# Module_blk.net
KiCad netlist of a schematic drawn in Altium Designer
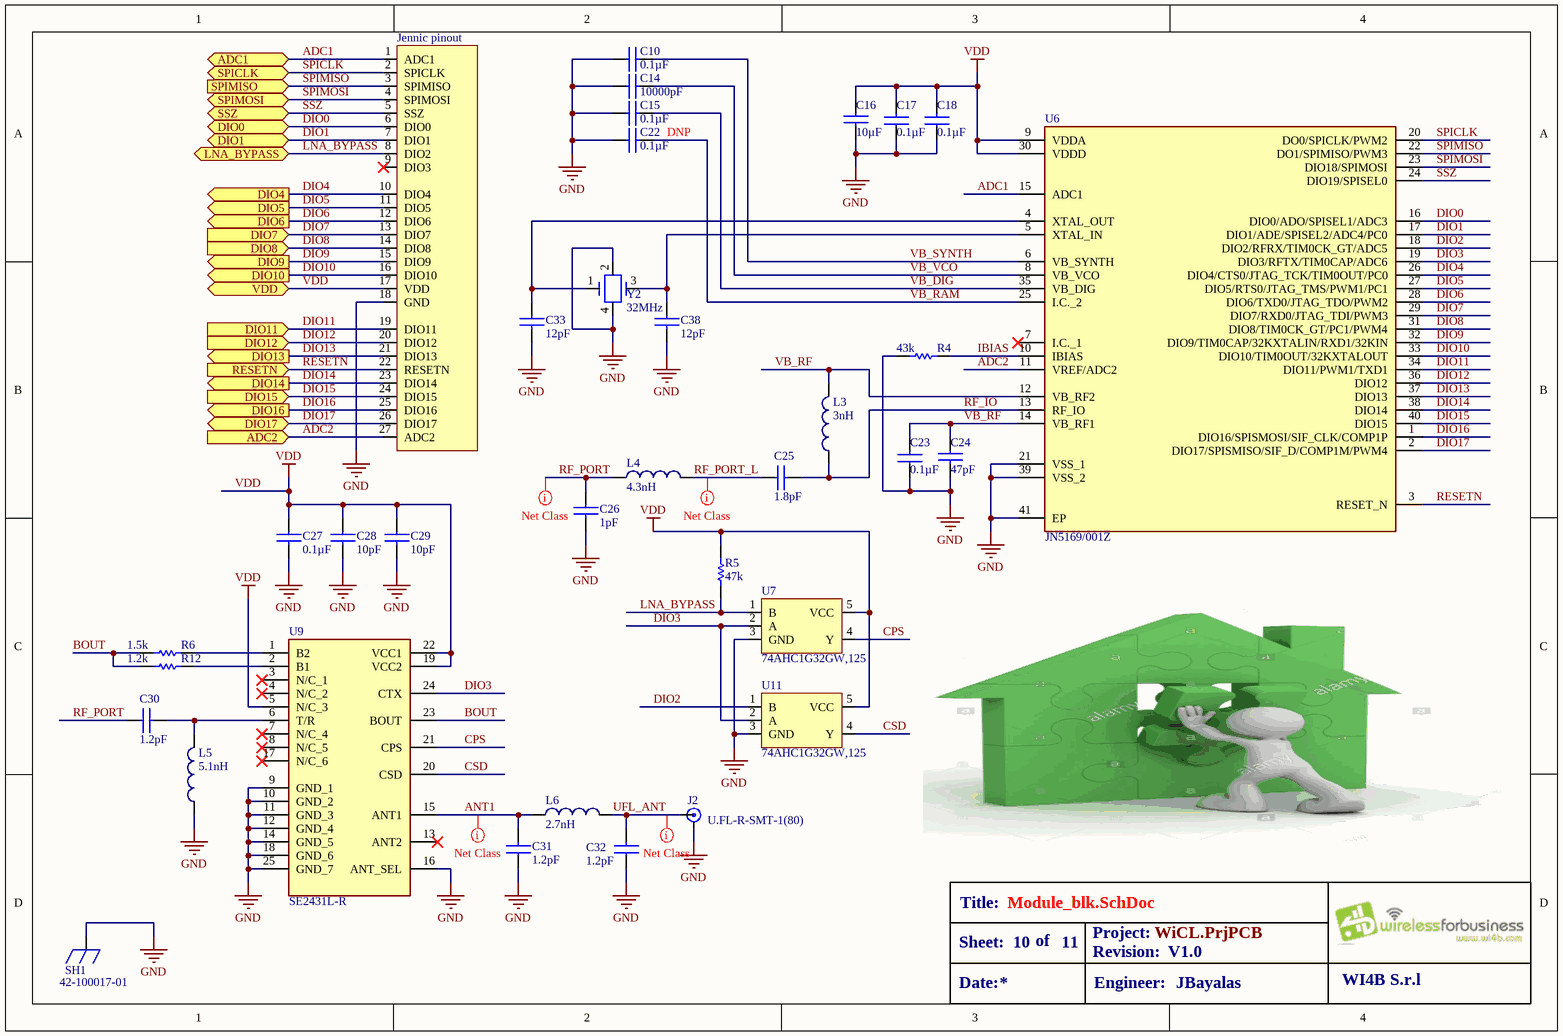
[diagram p0: Module_blk.SchDoc]

(export (version "E")
  (design (tool "Eeschema 10.0.6"))
  (components
    (comp (ref "C10")
      (value "0.1µF")
      (footprint "C0402")
      (description "CAP CER 0.1UF 10V 10% X5R 0402")
      (fields (field (name "MPN") "GRM155R61A104KA01D"))
      (libsource (lib "Capacitor") (part "GRM155R61A104KA01D"))
    )
    (comp (ref "C14")
      (value "10000pF")
      (footprint "C0402")
      (description "CAP CER 10000PF 25V X7R 0402")
      (fields (field (name "MPN") "GRM155R71E103KA01D"))
      (libsource (lib "Capacitor") (part "GRM155R71E103KA01D"))
    )
    (comp (ref "C15")
      (value "0.1µF")
      (footprint "C0402")
      (description "CAP CER 0.1UF 10V 10% X5R 0402")
      (fields (field (name "MPN") "GRM155R61A104KA01D"))
      (libsource (lib "Capacitor") (part "GRM155R61A104KA01D"))
    )
    (comp (ref "C16")
      (value "10µF")
      (footprint "CAPC2012X135N")
      (description "CAP CER 10UF 10V X5R 0805")
      (fields (field (name "MPN") "GRT21BR61A106KE01L"))
      (libsource (lib "Capacitor") (part "GRT21BR61A106KE01L"))
    )
    (comp (ref "C17")
      (value "0.1µF")
      (footprint "C0402")
      (description "CAP CER 0.1UF 10V 10% X5R 0402")
      (fields (field (name "MPN") "GRM155R61A104KA01D"))
      (libsource (lib "Capacitor") (part "GRM155R61A104KA01D"))
    )
    (comp (ref "C18")
      (value "0.1µF")
      (footprint "C0402")
      (description "CAP CER 0.1UF 10V 10% X5R 0402")
      (fields (field (name "MPN") "GRM155R61A104KA01D"))
      (libsource (lib "Capacitor") (part "GRM155R61A104KA01D"))
    )
    (comp (ref "C22")
      (value "0.1µF")
      (footprint "C0402")
      (description "CAP CER 0.1UF 10V 10% X5R 0402")
      (fields (field (name "MPN") "GRM155R61A104KA01D") (field (name "LOAD") "DNP"))
      (libsource (lib "Capacitor") (part "GRM155R61A104KA01D"))
    )
    (comp (ref "C23")
      (value "0.1µF")
      (footprint "C0402")
      (description "CAP CER 0.1UF 10V 10% X5R 0402")
      (fields (field (name "MPN") "GRM155R61A104KA01D"))
      (libsource (lib "Capacitor") (part "GRM155R61A104KA01D"))
    )
    (comp (ref "C24")
      (value "47pF")
      (footprint "CAPC1005X55N")
      (description "CAP CER 47PF 50V C0G/NP0 0402")
      (fields (field (name "MPN") "GRM1555C1H470JA01D"))
      (libsource (lib "Capacitor") (part "GRM1555C1H470JA01D"))
    )
    (comp (ref "C25")
      (value "1.8pF")
      (footprint "CAPC1005X55N")
      (description "CAP CER 1.8PF 50V C0G/NP0 0402")
      (fields (field (name "MPN") "GRM1555C1H1R8CA01D"))
      (libsource (lib "Capacitor") (part "GRM1555C1H1R8CA01D"))
    )
    (comp (ref "C26")
      (value "1pF")
      (footprint "CAPC1005X55N")
      (description "CAP CER 1PF 50V C0G/NP0 0402")
      (fields (field (name "MPN") "GRM1555C1H1R0CA01D"))
      (libsource (lib "Capacitor") (part "GRM1555C1H1R0CA01D"))
    )
    (comp (ref "C27")
      (value "0.1µF")
      (footprint "C0402")
      (description "CAP CER 0.1UF 10V 10% X5R 0402")
      (fields (field (name "MPN") "GRM155R61A104KA01D"))
      (libsource (lib "Capacitor") (part "GRM155R61A104KA01D"))
    )
    (comp (ref "C28")
      (value "10pF")
      (footprint "C0402")
      (description "CAP CER 10PF 50V 5% NP0 0402")
      (fields (field (name "MPN") "GRM1555C1H100JA01D"))
      (libsource (lib "Capacitor") (part "GRM1555C1H100JA01D"))
    )
    (comp (ref "C29")
      (value "10pF")
      (footprint "C0402")
      (description "CAP CER 10PF 50V 5% NP0 0402")
      (fields (field (name "MPN") "GRM1555C1H100JA01D"))
      (libsource (lib "Capacitor") (part "GRM1555C1H100JA01D"))
    )
    (comp (ref "C30")
      (value "1.2pF")
      (footprint "CAPC1005X55N")
      (description "CAP CER 1.2PF 50V C0G/NP0 0402")
      (fields (field (name "MPN") "GRM1555C1H1R2CA01D"))
      (libsource (lib "Capacitor") (part "GRM1555C1H1R2CA01D"))
    )
    (comp (ref "C31")
      (value "1.2pF")
      (footprint "CAPC1005X55N")
      (description "CAP CER 1.2PF 50V C0G/NP0 0402")
      (fields (field (name "MPN") "GRM1555C1H1R2CA01D"))
      (libsource (lib "Capacitor") (part "GRM1555C1H1R2CA01D"))
    )
    (comp (ref "C32")
      (value "1.2pF")
      (footprint "CAPC1005X55N")
      (description "CAP CER 1.2PF 50V C0G/NP0 0402")
      (fields (field (name "MPN") "GRM1555C1H1R2CA01D"))
      (libsource (lib "Capacitor") (part "GRM1555C1H1R2CA01D"))
    )
    (comp (ref "C33")
      (value "12pF")
      (footprint "CAPC1005X55N")
      (description "CAP CER 12PF 50V C0G/NP0 0402")
      (fields (field (name "MPN") "GRM1555C1H120JA01D"))
      (libsource (lib "Capacitor") (part "GRM1555C1H120JA01D"))
    )
    (comp (ref "C38")
      (value "12pF")
      (footprint "CAPC1005X55N")
      (description "CAP CER 12PF 50V C0G/NP0 0402")
      (fields (field (name "MPN") "GRM1555C1H120JA01D"))
      (libsource (lib "Capacitor") (part "GRM1555C1H120JA01D"))
    )
    (comp (ref "J2")
      (value "U.FL-R-SMT-1(80)")
      (footprint "HIROSE_U.FL-R-SMT")
      (description "RF Connectors / Coaxial Connectors SMT MALE RECEPT AU")
      (libsource (lib "Connector") (part "U.FL-R-SMT-1(80)"))
    )
    (comp (ref "Jennic pinout")
      (value "Jennic pinout")
      (footprint "JN516X PINOUT")
      (libsource (lib "Miscellaneous") (part "Jennic pinout"))
    )
    (comp (ref "L3")
      (value "3nH")
      (footprint "INDC1005X45N")
      (description "FIXED IND 3NH 190MA 400 MOHM SMD")
      (fields (field (name "MPN") "LQP15MN3N0B02D"))
      (libsource (lib "Inductor") (part "LQP15MN3N0B02D"))
    )
    (comp (ref "L4")
      (value "4.3nH")
      (footprint "INDC1005X45N")
      (description "FIXED IND 4.3NH 160MA 600 MOHM")
      (fields (field (name "MPN") "LQP15MN4N3B02D"))
      (libsource (lib "Inductor") (part "LQP15MN4N3B02D"))
    )
    (comp (ref "L5")
      (value "5.1nH")
      (footprint "INDC1005X45N")
      (description "Inductor RF Chip ThFIXED IND 5.1NH 140MA 700 MOHM")
      (fields (field (name "MPN") "LQP15MN5N1B02D"))
      (libsource (lib "Inductor") (part "LQP15MN5N1B02D"))
    )
    (comp (ref "L6")
      (value "2.7nH")
      (footprint "INDC1005X45N")
      (description "FIXED IND 2.7NH 220MA 300 MOHM")
      (fields (field (name "MPN") "LQP15MN2N7B02D"))
      (libsource (lib "Inductor") (part "LQP15MN2N7B02D"))
    )
    (comp (ref "R4")
      (value "43k")
      (footprint "RESC1005X40N")
      (description "RES SMD 43K OHM 1% 1/16W 0402")
      (fields (field (name "MPN") "RC0402FR-0743KL"))
      (libsource (lib "Res") (part "RC0402FR-0743KL"))
    )
    (comp (ref "R5")
      (value "47k")
      (footprint "R0402")
      (description "RES SMD 47K OHM 1% 1/16W 0402")
      (fields (field (name "MPN") "RC0402FR-0747KL"))
      (libsource (lib "Res") (part "RC0402FR-0747KL"))
    )
    (comp (ref "R6")
      (value "1.5k")
      (footprint "RESC1005X40N")
      (description "RES SMD 1.5K OHM 1% 1/16W 0402")
      (fields (field (name "MPN") "RC0402FR-071K5L"))
      (libsource (lib "Res") (part "RC0402FR-071K5L"))
    )
    (comp (ref "R12")
      (value "1.2k")
      (footprint "RESC1005X40N")
      (description "RES SMD 1.2K OHM 1% 1/16W 0402")
      (fields (field (name "MPN") "RC0402FR-071K2L"))
      (libsource (lib "Res") (part "RC0402FR-071K2L"))
    )
    (comp (ref "SH1")
      (value "42-100017-01")
      (footprint "42-100017-01(Shield)")
      (description "Shield")
      (libsource (lib "Miscellaneous") (part "42-100017-01"))
    )
    (comp (ref "U6")
      (value "JN5169/001Z")
      (footprint "QFN50P600X600X100-41N")
      (description "IC RF TXRX+MCU 802.15.4 40-VFQFN")
      (libsource (lib "IC") (part "JN5169/001Z"))
    )
    (comp (ref "U7")
      (value "74AHC1G32GW,125")
      (footprint "SOT65P210X110-5N")
      (description "IC GATE OR 1CH 2-INP 5TSSOP")
      (libsource (lib "IC") (part "74AHC1G32GW,125"))
    )
    (comp (ref "U9")
      (value "SE2431L-R")
      (footprint "QFN40P300X400X90-25N-D")
      (description "IC RF FRONT END MOD 2.4GHZ 24QFN")
      (libsource (lib "IC") (part "SE2431L-R"))
    )
    (comp (ref "U11")
      (value "74AHC1G32GW,125")
      (footprint "SOT65P210X110-5N")
      (description "IC GATE OR 1CH 2-INP 5TSSOP")
      (libsource (lib "IC") (part "74AHC1G32GW,125"))
    )
    (comp (ref "Y2")
      (value "32MHz")
      (footprint "OSCCC320X250X80L75X100N")
      (description "CRYSTAL 32.0000MHZ 9PF SMD")
      (fields (field (name "MPN") "ABM8-32.000MHZ-9-D1G-T"))
      (libsource (lib "Crystal") (part "ABM8-32.000MHZ-9-D1G-T"))
    )
  )
  (nets
    (net (code "1") (name "/ADC1") (class "Default")
      (node (ref "Jennic pinout") (pin "1") (pinfunction "ADC1_1") (pintype "passive"))
      (node (ref "U6") (pin "15") (pinfunction "ADC1_15") (pintype "passive"))
    )
    (net (code "2") (name "/ADC2") (class "Default")
      (node (ref "Jennic pinout") (pin "27") (pinfunction "ADC2_27") (pintype "passive"))
      (node (ref "U6") (pin "11") (pinfunction "VREF/ADC2_11") (pintype "passive"))
    )
    (net (code "3") (name "/ANT1") (class "Default")
      (node (ref "C31") (pin "2") (pinfunction "2_2") (pintype "passive"))
      (node (ref "L6") (pin "2") (pinfunction "2_2") (pintype "passive"))
      (node (ref "U9") (pin "15") (pinfunction "ANT1_15") (pintype "passive"))
    )
    (net (code "4") (name "/BOUT") (class "Default")
      (node (ref "R12") (pin "1") (pinfunction "1_1") (pintype "passive"))
      (node (ref "R6") (pin "1") (pinfunction "1_1") (pintype "passive"))
      (node (ref "U9") (pin "23") (pinfunction "BOUT_23") (pintype "passive"))
    )
    (net (code "5") (name "/CPS") (class "Default")
      (node (ref "U7") (pin "4") (pinfunction "Y_4") (pintype "passive"))
      (node (ref "U9") (pin "21") (pinfunction "CPS_21") (pintype "passive"))
    )
    (net (code "6") (name "/CSD") (class "Default")
      (node (ref "U11") (pin "4") (pinfunction "Y_4") (pintype "passive"))
      (node (ref "U9") (pin "20") (pinfunction "CSD_20") (pintype "passive"))
    )
    (net (code "7") (name "/DIO0") (class "Default")
      (node (ref "Jennic pinout") (pin "6") (pinfunction "DIO0_6") (pintype "passive"))
      (node (ref "U6") (pin "16") (pinfunction "DIO0/ADO/SPISEL1/ADC3_16") (pintype "passive"))
    )
    (net (code "8") (name "/DIO1") (class "Default")
      (node (ref "Jennic pinout") (pin "7") (pinfunction "DIO1_7") (pintype "passive"))
      (node (ref "U6") (pin "17") (pinfunction "DIO1/ADE/SPISEL2/ADC4/PC0_17") (pintype "passive"))
    )
    (net (code "9") (name "/DIO2") (class "Default")
      (node (ref "U11") (pin "1") (pinfunction "B_1") (pintype "passive"))
      (node (ref "U6") (pin "18") (pinfunction "DIO2/RFRX/TIM0CK_GT/ADC5_18") (pintype "passive"))
    )
    (net (code "10") (name "/DIO3") (class "Default")
      (node (ref "U11") (pin "2") (pinfunction "A_2") (pintype "passive"))
      (node (ref "U6") (pin "19") (pinfunction "DIO3/RFTX/TIM0CAP/ADC6_19") (pintype "passive"))
      (node (ref "U7") (pin "2") (pinfunction "A_2") (pintype "passive"))
      (node (ref "U9") (pin "24") (pinfunction "CTX_24") (pintype "passive"))
    )
    (net (code "11") (name "/DIO4") (class "Default")
      (node (ref "Jennic pinout") (pin "10") (pinfunction "DIO4_10") (pintype "passive"))
      (node (ref "U6") (pin "26") (pinfunction "DIO4/CTS0/JTAG_TCK/TIM0OUT/PC0_26") (pintype "passive"))
    )
    (net (code "12") (name "/DIO5") (class "Default")
      (node (ref "Jennic pinout") (pin "11") (pinfunction "DIO5_11") (pintype "passive"))
      (node (ref "U6") (pin "27") (pinfunction "DIO5/RTS0/JTAG_TMS/PWM1/PC1_27") (pintype "passive"))
    )
    (net (code "13") (name "/DIO6") (class "Default")
      (node (ref "Jennic pinout") (pin "12") (pinfunction "DIO6_12") (pintype "passive"))
      (node (ref "U6") (pin "28") (pinfunction "DIO6/TXD0/JTAG_TDO/PWM2_28") (pintype "passive"))
    )
    (net (code "14") (name "/DIO7") (class "Default")
      (node (ref "Jennic pinout") (pin "13") (pinfunction "DIO7_13") (pintype "passive"))
      (node (ref "U6") (pin "29") (pinfunction "DIO7/RXD0/JTAG_TDI/PWM3_29") (pintype "passive"))
    )
    (net (code "15") (name "/DIO8") (class "Default")
      (node (ref "Jennic pinout") (pin "14") (pinfunction "DIO8_14") (pintype "passive"))
      (node (ref "U6") (pin "31") (pinfunction "DIO8/TIM0CK_GT/PC1/PWM4_31") (pintype "passive"))
    )
    (net (code "16") (name "/DIO9") (class "Default")
      (node (ref "Jennic pinout") (pin "15") (pinfunction "DIO9_15") (pintype "passive"))
      (node (ref "U6") (pin "32") (pinfunction "DIO9/TIM0CAP/32KXTALIN/RXD1/32KIN_32") (pintype "passive"))
    )
    (net (code "17") (name "/DIO10") (class "Default")
      (node (ref "Jennic pinout") (pin "16") (pinfunction "DIO10_16") (pintype "passive"))
      (node (ref "U6") (pin "33") (pinfunction "DIO10/TIM0OUT/32KXTALOUT_33") (pintype "passive"))
    )
    (net (code "18") (name "/DIO11") (class "Default")
      (node (ref "Jennic pinout") (pin "19") (pinfunction "DIO11_19") (pintype "passive"))
      (node (ref "U6") (pin "34") (pinfunction "DIO11/PWM1/TXD1_34") (pintype "passive"))
    )
    (net (code "19") (name "/DIO12") (class "Default")
      (node (ref "Jennic pinout") (pin "20") (pinfunction "DIO12_20") (pintype "passive"))
      (node (ref "U6") (pin "36") (pinfunction "DIO12_36") (pintype "passive"))
    )
    (net (code "20") (name "/DIO13") (class "Default")
      (node (ref "Jennic pinout") (pin "21") (pinfunction "DIO13_21") (pintype "passive"))
      (node (ref "U6") (pin "37") (pinfunction "DIO13_37") (pintype "passive"))
    )
    (net (code "21") (name "/DIO14") (class "Default")
      (node (ref "Jennic pinout") (pin "23") (pinfunction "DIO14_23") (pintype "passive"))
      (node (ref "U6") (pin "38") (pinfunction "DIO14_38") (pintype "passive"))
    )
    (net (code "22") (name "/DIO15") (class "Default")
      (node (ref "Jennic pinout") (pin "24") (pinfunction "DIO15_24") (pintype "passive"))
      (node (ref "U6") (pin "40") (pinfunction "DIO15_40") (pintype "passive"))
    )
    (net (code "23") (name "/DIO16") (class "Default")
      (node (ref "Jennic pinout") (pin "25") (pinfunction "DIO16_25") (pintype "passive"))
      (node (ref "U6") (pin "1") (pinfunction "DIO16/SPISMOSI/SIF_CLK/COMP1P_1") (pintype "passive"))
    )
    (net (code "24") (name "/DIO17") (class "Default")
      (node (ref "Jennic pinout") (pin "26") (pinfunction "DIO17_26") (pintype "passive"))
      (node (ref "U6") (pin "2") (pinfunction "DIO17/SPISMISO/SIF_D/COMP1M/PWM4_2") (pintype "passive"))
    )
    (net (code "25") (name "/IBIAS") (class "Default")
      (node (ref "R4") (pin "2") (pinfunction "2_2") (pintype "passive"))
      (node (ref "U6") (pin "10") (pinfunction "IBIAS_10") (pintype "passive"))
    )
    (net (code "26") (name "/LNA_BYPASS") (class "Default")
      (node (ref "Jennic pinout") (pin "8") (pinfunction "DIO2_8") (pintype "passive"))
      (node (ref "R5") (pin "1") (pinfunction "1_1") (pintype "passive"))
      (node (ref "U7") (pin "1") (pinfunction "B_1") (pintype "passive"))
    )
    (net (code "27") (name "/RESETN") (class "Default")
      (node (ref "Jennic pinout") (pin "22") (pinfunction "RESETN_22") (pintype "passive"))
      (node (ref "U6") (pin "3") (pinfunction "RESET_N_3") (pintype "passive"))
    )
    (net (code "28") (name "/RF_IO") (class "Default")
      (node (ref "C25") (pin "2") (pinfunction "2_2") (pintype "passive"))
      (node (ref "L3") (pin "2") (pinfunction "2_2") (pintype "passive"))
      (node (ref "U6") (pin "13") (pinfunction "RF_IO_13") (pintype "passive"))
    )
    (net (code "29") (name "/RF_PORT") (class "Default")
      (node (ref "C26") (pin "1") (pinfunction "1_1") (pintype "passive"))
      (node (ref "C30") (pin "1") (pinfunction "1_1") (pintype "passive"))
      (node (ref "L4") (pin "2") (pinfunction "2_2") (pintype "passive"))
    )
    (net (code "30") (name "/RF_PORT_L") (class "Default")
      (node (ref "C25") (pin "1") (pinfunction "1_1") (pintype "passive"))
      (node (ref "L4") (pin "1") (pinfunction "1_1") (pintype "passive"))
    )
    (net (code "31") (name "/SPICLK") (class "Default")
      (node (ref "Jennic pinout") (pin "2") (pinfunction "SPICLK_2") (pintype "passive"))
      (node (ref "U6") (pin "20") (pinfunction "DO0/SPICLK/PWM2_20") (pintype "passive"))
    )
    (net (code "32") (name "/SPIMISO") (class "Default")
      (node (ref "Jennic pinout") (pin "3") (pinfunction "SPIMISO_3") (pintype "passive"))
      (node (ref "U6") (pin "22") (pinfunction "DO1/SPIMISO/PWM3_22") (pintype "passive"))
    )
    (net (code "33") (name "/SPIMOSI") (class "Default")
      (node (ref "Jennic pinout") (pin "4") (pinfunction "SPIMOSI_4") (pintype "passive"))
      (node (ref "U6") (pin "23") (pinfunction "DIO18/SPIMOSI_23") (pintype "passive"))
    )
    (net (code "34") (name "/SSZ") (class "Default")
      (node (ref "Jennic pinout") (pin "5") (pinfunction "SSZ_5") (pintype "passive"))
      (node (ref "U6") (pin "24") (pinfunction "DIO19/SPISEL0_24") (pintype "passive"))
    )
    (net (code "35") (name "/UFL_ANT") (class "Default")
      (node (ref "C32") (pin "2") (pinfunction "2_2") (pintype "passive"))
      (node (ref "J2") (pin "1") (pinfunction "SIGNAL_1") (pintype "passive"))
      (node (ref "L6") (pin "1") (pinfunction "1_1") (pintype "passive"))
    )
    (net (code "36") (name "/VB_DIG") (class "Default")
      (node (ref "C15") (pin "2") (pinfunction "2_2") (pintype "passive"))
      (node (ref "U6") (pin "35") (pinfunction "VB_DIG_35") (pintype "passive"))
    )
    (net (code "37") (name "/VB_RAM") (class "Default")
      (node (ref "C22") (pin "2") (pinfunction "2_2") (pintype "passive"))
      (node (ref "U6") (pin "25") (pinfunction "I.C._2_25") (pintype "passive"))
    )
    (net (code "38") (name "/VB_RF") (class "Default")
      (node (ref "C23") (pin "2") (pinfunction "2_2") (pintype "passive"))
      (node (ref "C24") (pin "1") (pinfunction "1_1") (pintype "passive"))
      (node (ref "L3") (pin "1") (pinfunction "1_1") (pintype "passive"))
      (node (ref "U6") (pin "12") (pinfunction "VB_RF2_12") (pintype "passive"))
      (node (ref "U6") (pin "14") (pinfunction "VB_RF1_14") (pintype "passive"))
    )
    (net (code "39") (name "/VB_SYNTH") (class "Default")
      (node (ref "C10") (pin "2") (pinfunction "2_2") (pintype "passive"))
      (node (ref "U6") (pin "6") (pinfunction "VB_SYNTH_6") (pintype "passive"))
    )
    (net (code "40") (name "/VB_VCO") (class "Default")
      (node (ref "C14") (pin "2") (pinfunction "2_2") (pintype "passive"))
      (node (ref "U6") (pin "8") (pinfunction "VB_VCO_8") (pintype "passive"))
    )
    (net (code "41") (name "GND") (class "Default")
      (node (ref "C10") (pin "1") (pinfunction "1_1") (pintype "passive"))
      (node (ref "C14") (pin "1") (pinfunction "1_1") (pintype "passive"))
      (node (ref "C15") (pin "1") (pinfunction "1_1") (pintype "passive"))
      (node (ref "C16") (pin "2") (pinfunction "2_2") (pintype "passive"))
      (node (ref "C17") (pin "1") (pinfunction "1_1") (pintype "passive"))
      (node (ref "C18") (pin "1") (pinfunction "1_1") (pintype "passive"))
      (node (ref "C22") (pin "1") (pinfunction "1_1") (pintype "passive"))
      (node (ref "C23") (pin "1") (pinfunction "1_1") (pintype "passive"))
      (node (ref "C24") (pin "2") (pinfunction "2_2") (pintype "passive"))
      (node (ref "C26") (pin "2") (pinfunction "2_2") (pintype "passive"))
      (node (ref "C27") (pin "2") (pinfunction "2_2") (pintype "passive"))
      (node (ref "C28") (pin "2") (pinfunction "2_2") (pintype "passive"))
      (node (ref "C29") (pin "2") (pinfunction "2_2") (pintype "passive"))
      (node (ref "C31") (pin "1") (pinfunction "1_1") (pintype "passive"))
      (node (ref "C32") (pin "1") (pinfunction "1_1") (pintype "passive"))
      (node (ref "C33") (pin "2") (pinfunction "2_2") (pintype "passive"))
      (node (ref "C38") (pin "2") (pinfunction "2_2") (pintype "passive"))
      (node (ref "J2") (pin "2") (pinfunction "GND_2") (pintype "passive"))
      (node (ref "Jennic pinout") (pin "18") (pinfunction "GND_18") (pintype "passive"))
      (node (ref "L5") (pin "2") (pinfunction "2_2") (pintype "passive"))
      (node (ref "R4") (pin "1") (pinfunction "1_1") (pintype "passive"))
      (node (ref "SH1") (pin "1") (pinfunction "1_1") (pintype "passive"))
      (node (ref "U11") (pin "3") (pinfunction "GND_3") (pintype "passive"))
      (node (ref "U6") (pin "21") (pinfunction "VSS_1_21") (pintype "passive"))
      (node (ref "U6") (pin "39") (pinfunction "VSS_2_39") (pintype "passive"))
      (node (ref "U6") (pin "41") (pinfunction "EP_41") (pintype "passive"))
      (node (ref "U7") (pin "3") (pinfunction "GND_3") (pintype "passive"))
      (node (ref "U9") (pin "10") (pinfunction "GND_2_10") (pintype "passive"))
      (node (ref "U9") (pin "11") (pinfunction "GND_3_11") (pintype "passive"))
      (node (ref "U9") (pin "12") (pinfunction "GND_4_12") (pintype "passive"))
      (node (ref "U9") (pin "14") (pinfunction "GND_5_14") (pintype "passive"))
      (node (ref "U9") (pin "16") (pinfunction "ANT_SEL_16") (pintype "passive"))
      (node (ref "U9") (pin "18") (pinfunction "GND_6_18") (pintype "passive"))
      (node (ref "U9") (pin "25") (pinfunction "GND_7_25") (pintype "passive"))
      (node (ref "U9") (pin "9") (pinfunction "GND_1_9") (pintype "passive"))
      (node (ref "Y2") (pin "2") (pinfunction "2_2") (pintype "passive"))
      (node (ref "Y2") (pin "4") (pinfunction "4_4") (pintype "passive"))
    )
    (net (code "42") (name "Net-(U6-XTAL_IN)") (class "Default")
      (node (ref "C38") (pin "1") (pinfunction "1_1") (pintype "passive"))
      (node (ref "U6") (pin "5") (pinfunction "XTAL_IN_5") (pintype "passive"))
      (node (ref "Y2") (pin "3") (pinfunction "3_3") (pintype "passive"))
    )
    (net (code "43") (name "Net-(U6-XTAL_OUT)") (class "Default")
      (node (ref "C33") (pin "1") (pinfunction "1_1") (pintype "passive"))
      (node (ref "U6") (pin "4") (pinfunction "XTAL_OUT_4") (pintype "passive"))
      (node (ref "Y2") (pin "1") (pinfunction "1_1") (pintype "passive"))
    )
    (net (code "44") (name "Net-(U9-B1)") (class "Default")
      (node (ref "R12") (pin "2") (pinfunction "2_2") (pintype "passive"))
      (node (ref "U9") (pin "2") (pinfunction "B1_2") (pintype "passive"))
    )
    (net (code "45") (name "Net-(U9-B2)") (class "Default")
      (node (ref "R6") (pin "2") (pinfunction "2_2") (pintype "passive"))
      (node (ref "U9") (pin "1") (pinfunction "B2_1") (pintype "passive"))
    )
    (net (code "46") (name "Net-(U9-T{slash}R)") (class "Default")
      (node (ref "C30") (pin "2") (pinfunction "2_2") (pintype "passive"))
      (node (ref "L5") (pin "1") (pinfunction "1_1") (pintype "passive"))
      (node (ref "U9") (pin "6") (pinfunction "T/R_6") (pintype "passive"))
    )
    (net (code "47") (name "VDD") (class "Default")
      (node (ref "C16") (pin "1") (pinfunction "1_1") (pintype "passive"))
      (node (ref "C17") (pin "2") (pinfunction "2_2") (pintype "passive"))
      (node (ref "C18") (pin "2") (pinfunction "2_2") (pintype "passive"))
      (node (ref "C27") (pin "1") (pinfunction "1_1") (pintype "passive"))
      (node (ref "C28") (pin "1") (pinfunction "1_1") (pintype "passive"))
      (node (ref "C29") (pin "1") (pinfunction "1_1") (pintype "passive"))
      (node (ref "Jennic pinout") (pin "17") (pinfunction "VDD_17") (pintype "passive"))
      (node (ref "R5") (pin "2") (pinfunction "2_2") (pintype "passive"))
      (node (ref "U11") (pin "5") (pinfunction "VCC_5") (pintype "passive"))
      (node (ref "U6") (pin "30") (pinfunction "VDDD_30") (pintype "passive"))
      (node (ref "U6") (pin "9") (pinfunction "VDDA_9") (pintype "passive"))
      (node (ref "U7") (pin "5") (pinfunction "VCC_5") (pintype "passive"))
      (node (ref "U9") (pin "19") (pinfunction "VCC2_19") (pintype "passive"))
      (node (ref "U9") (pin "22") (pinfunction "VCC1_22") (pintype "passive"))
      (node (ref "U9") (pin "5") (pinfunction "N/C_3_5") (pintype "passive"))
    )
    (net (code "48") (name "unconnected-(Jennic pinout-DIO3-Pad9)") (class "Default")
      (node (ref "Jennic pinout") (pin "9") (pinfunction "DIO3_9") (pintype "passive+no_connect"))
    )
    (net (code "49") (name "unconnected-(U6-I.C._1-Pad7)") (class "Default")
      (node (ref "U6") (pin "7") (pinfunction "I.C._1_7") (pintype "passive+no_connect"))
    )
    (net (code "50") (name "unconnected-(U9-ANT2-Pad13)") (class "Default")
      (node (ref "U9") (pin "13") (pinfunction "ANT2_13") (pintype "passive+no_connect"))
    )
    (net (code "51") (name "unconnected-(U9-N{slash}C_1-Pad3)") (class "Default")
      (node (ref "U9") (pin "3") (pinfunction "N/C_1_3") (pintype "passive+no_connect"))
    )
    (net (code "52") (name "unconnected-(U9-N{slash}C_2-Pad4)") (class "Default")
      (node (ref "U9") (pin "4") (pinfunction "N/C_2_4") (pintype "passive+no_connect"))
    )
    (net (code "53") (name "unconnected-(U9-N{slash}C_4-Pad7)") (class "Default")
      (node (ref "U9") (pin "7") (pinfunction "N/C_4_7") (pintype "passive+no_connect"))
    )
    (net (code "54") (name "unconnected-(U9-N{slash}C_5-Pad8)") (class "Default")
      (node (ref "U9") (pin "8") (pinfunction "N/C_5_8") (pintype "passive+no_connect"))
    )
    (net (code "55") (name "unconnected-(U9-N{slash}C_6-Pad17)") (class "Default")
      (node (ref "U9") (pin "17") (pinfunction "N/C_6_17") (pintype "passive+no_connect"))
    )
  )
)
